# BRAIN_Breakout_routed.net
KiCad netlist of a schematic drawn in EAGLE
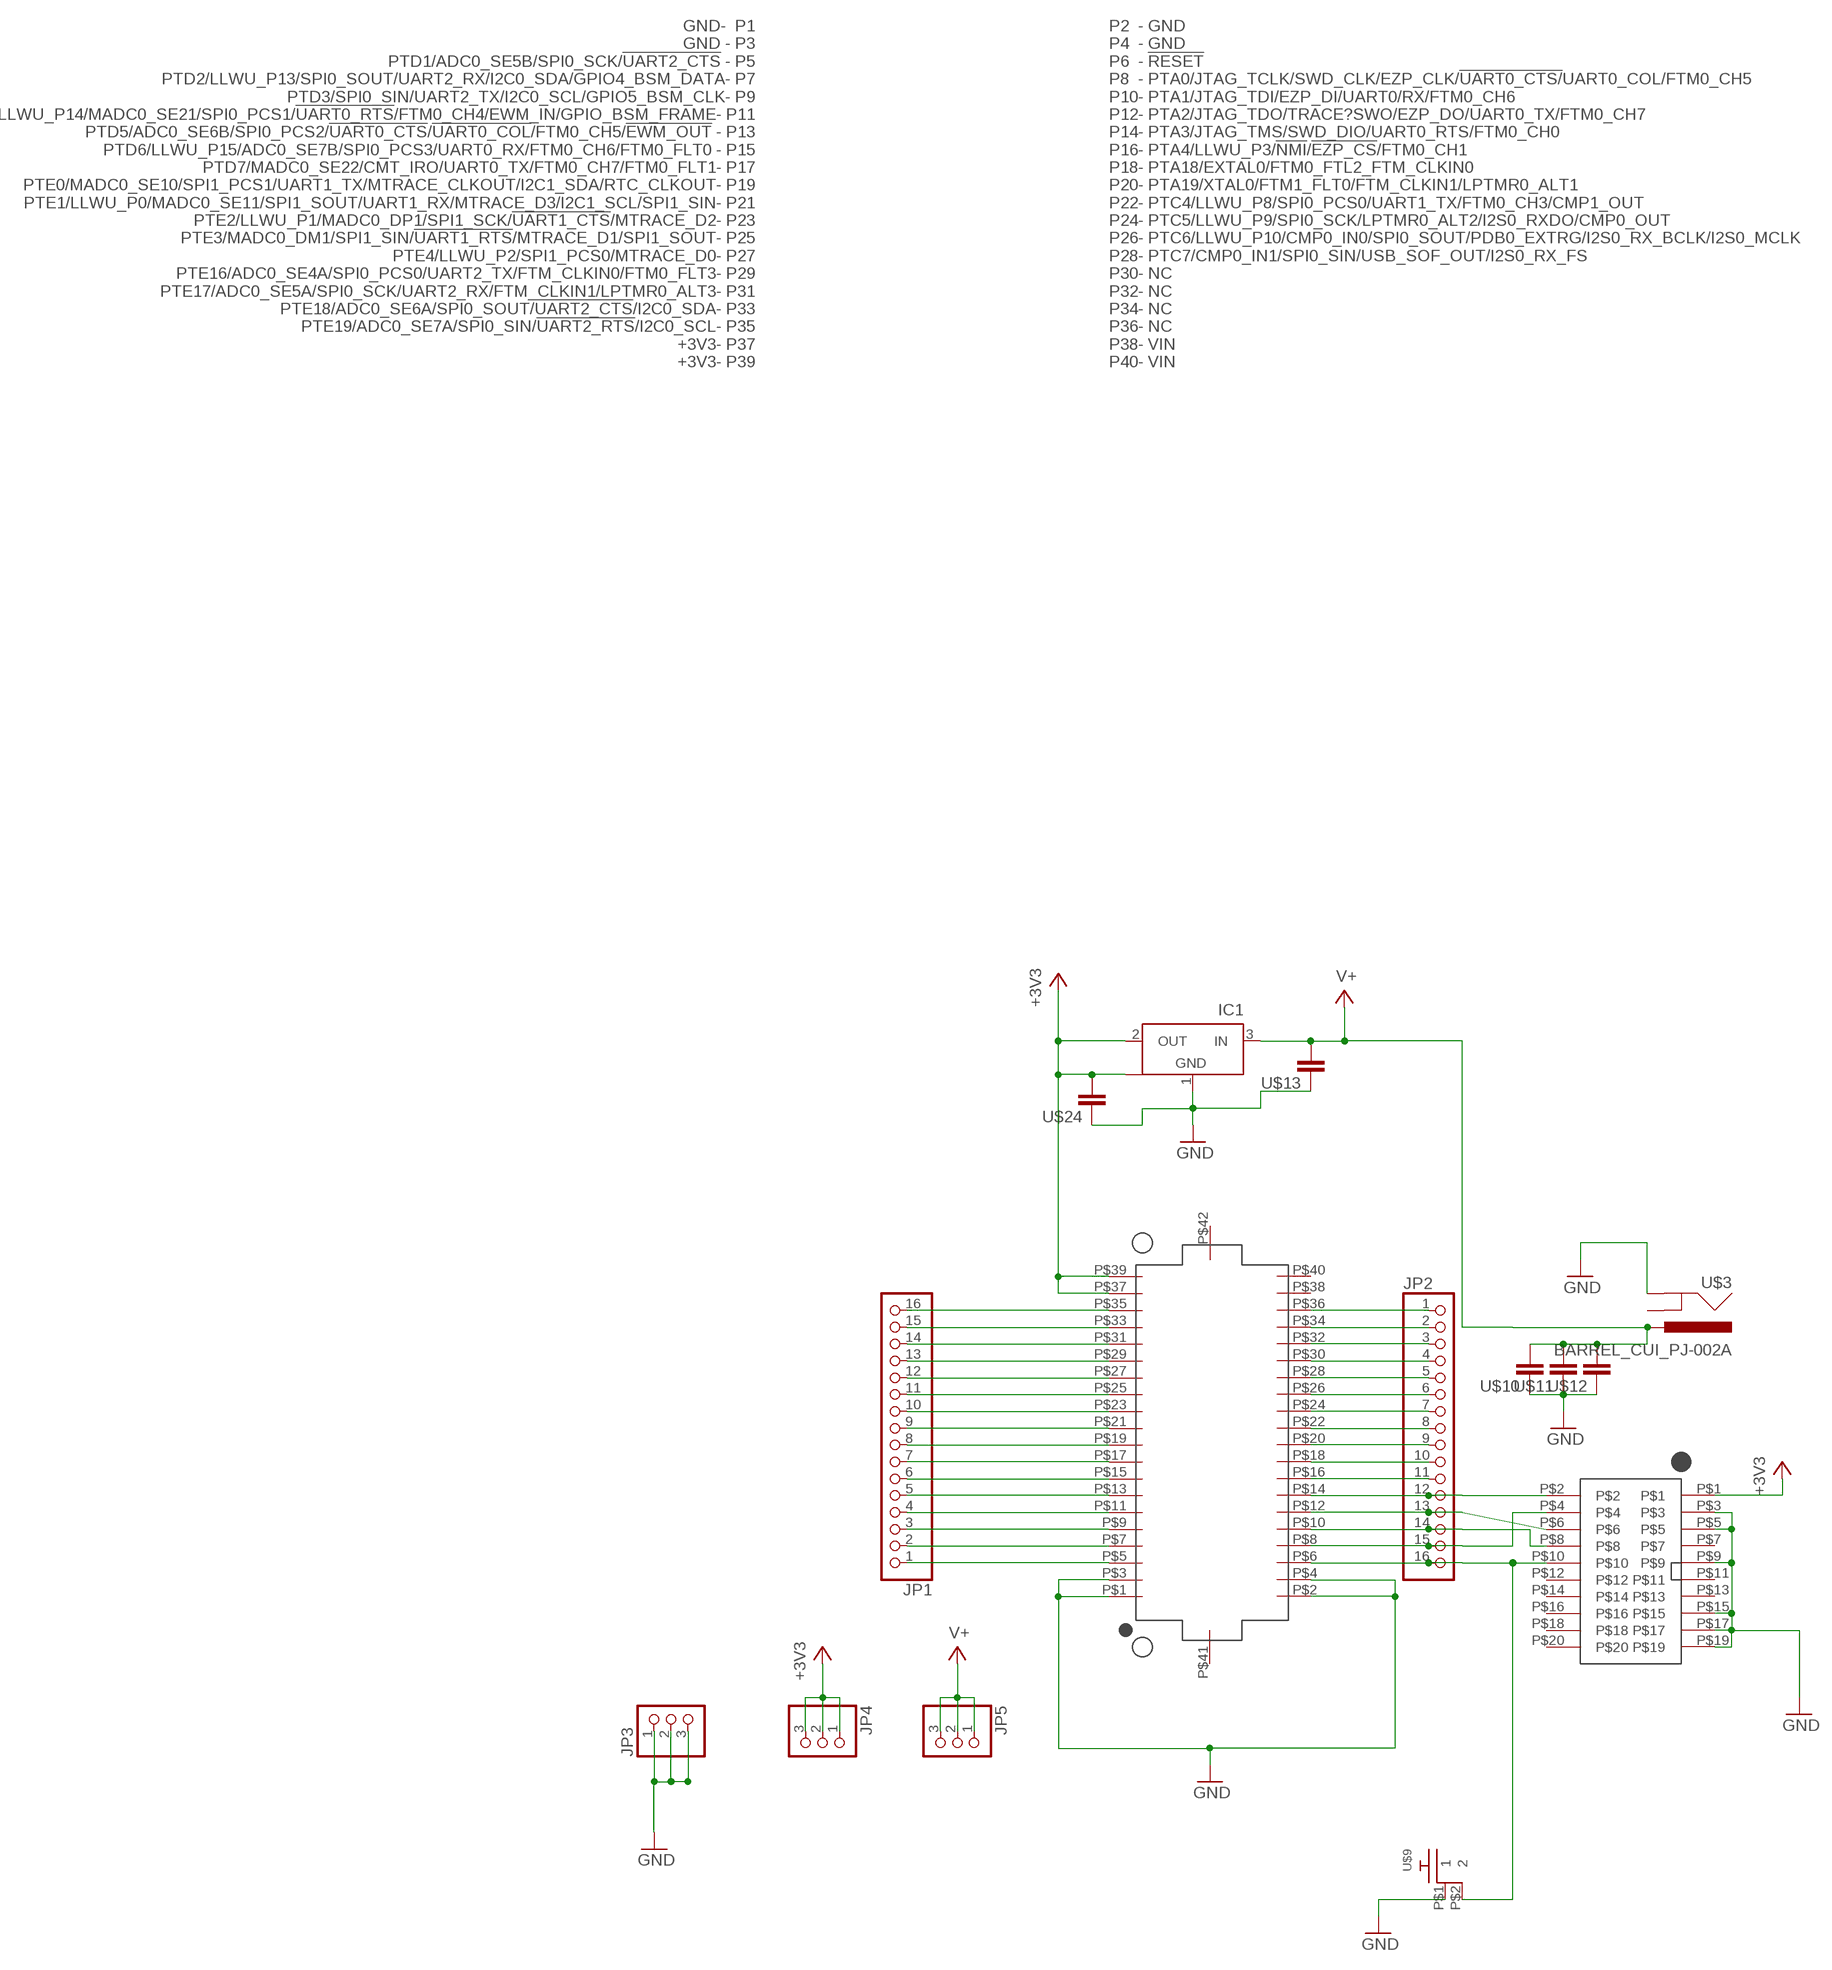
[diagram p0: schematic, sheet 1]

(export (version "E")
  (design (tool "Eeschema 10.0.6"))
  (components
    (comp (ref "IC1")
      (value "NCP1117ST33T3G_1")
      (footprint "eagle-import:SOT223")
      (fields (field (name "MFGN") "OnSemi") (field (name "MFGP") "NCP1117ST33T3G"))
      (libsource (lib "eagle-import") (part "NCP1117ST33T3G_1"))
    )
    (comp (ref "JP1")
      (value "PINHD-1X16")
      (footprint "eagle-import:1X16")
      (libsource (lib "eagle-import") (part "PINHD-1X16"))
    )
    (comp (ref "JP2")
      (value "PINHD-1X16")
      (footprint "eagle-import:1X16")
      (libsource (lib "eagle-import") (part "PINHD-1X16"))
    )
    (comp (ref "JP3")
      (value "PINHD-1X3")
      (footprint "eagle-import:1X03")
      (libsource (lib "eagle-import") (part "PINHD-1X3"))
    )
    (comp (ref "JP4")
      (value "PINHD-1X3")
      (footprint "eagle-import:1X03")
      (libsource (lib "eagle-import") (part "PINHD-1X3"))
    )
    (comp (ref "JP5")
      (value "PINHD-1X3")
      (footprint "eagle-import:1X03")
      (libsource (lib "eagle-import") (part "PINHD-1X3"))
    )
    (comp (ref "U$1")
      (value "DF12_F")
      (footprint "eagle-import:DF12_F")
      (libsource (lib "eagle-import") (part "DF12_F"))
    )
    (comp (ref "U$3")
      (value "BARREL_CUI_PJ-002A")
      (footprint "eagle-import:BARREL_CUI_PJ-002A")
      (libsource (lib "eagle-import") (part "BARREL_CUI_PJ-002A"))
    )
    (comp (ref "U$9")
      (value "RA_BUTTON")
      (footprint "eagle-import:RA_BUTTON")
      (libsource (lib "eagle-import") (part "RA_BUTTON"))
    )
    (comp (ref "U$10")
      (value "RF-C0805")
      (footprint "eagle-import:C0805")
      (libsource (lib "eagle-import") (part "RF-C0805"))
    )
    (comp (ref "U$11")
      (value "RF-C0805")
      (footprint "eagle-import:C0805")
      (libsource (lib "eagle-import") (part "RF-C0805"))
    )
    (comp (ref "U$12")
      (value "RF-C0805")
      (footprint "eagle-import:C0805")
      (libsource (lib "eagle-import") (part "RF-C0805"))
    )
    (comp (ref "U$13")
      (value "RF-C0805")
      (footprint "eagle-import:C0805")
      (libsource (lib "eagle-import") (part "RF-C0805"))
    )
    (comp (ref "U$19")
      (value "2X10JTAG")
      (footprint "eagle-import:2X10JTAG")
      (libsource (lib "eagle-import") (part "2X10JTAG"))
    )
    (comp (ref "U$24")
      (value "RF-C0805")
      (footprint "eagle-import:C0805")
      (libsource (lib "eagle-import") (part "RF-C0805"))
    )
  )
  (nets
    (net (code "1") (name "+3V3") (class "Default")
      (node (ref "IC1") (pin "2") (pinfunction "OUT_2") (pintype "power_in"))
      (node (ref "IC1") (pin "4") (pinfunction "OUT1_4") (pintype "power_in"))
      (node (ref "JP4") (pin "1") (pinfunction "1_1") (pintype "passive"))
      (node (ref "JP4") (pin "2") (pinfunction "2_2") (pintype "passive"))
      (node (ref "JP4") (pin "3") (pinfunction "3_3") (pintype "passive"))
      (node (ref "U$1") (pin "P$37") (pinfunction "+3V3_P$37") (pintype "bidirectional"))
      (node (ref "U$1") (pin "P$39") (pinfunction "+3V3_P$39") (pintype "bidirectional"))
      (node (ref "U$19") (pin "P$1") (pinfunction "P$1_P$1") (pintype "bidirectional"))
      (node (ref "U$24") (pin "2") (pinfunction "2_2") (pintype "passive"))
    )
    (net (code "2") (name "GND") (class "Default")
      (node (ref "IC1") (pin "1") (pinfunction "GND_1") (pintype "power_in"))
      (node (ref "JP3") (pin "1") (pinfunction "1_1") (pintype "passive"))
      (node (ref "JP3") (pin "2") (pinfunction "2_2") (pintype "passive"))
      (node (ref "JP3") (pin "3") (pinfunction "3_3") (pintype "passive"))
      (node (ref "U$1") (pin "P$1") (pinfunction "GND_P$1") (pintype "bidirectional"))
      (node (ref "U$1") (pin "P$2") (pinfunction "GND_P$2") (pintype "bidirectional"))
      (node (ref "U$1") (pin "P$3") (pinfunction "GND_P$3") (pintype "bidirectional"))
      (node (ref "U$1") (pin "P$4") (pinfunction "GND_P$4") (pintype "bidirectional"))
      (node (ref "U$10") (pin "1") (pinfunction "1_1") (pintype "passive"))
      (node (ref "U$11") (pin "1") (pinfunction "1_1") (pintype "passive"))
      (node (ref "U$12") (pin "1") (pinfunction "1_1") (pintype "passive"))
      (node (ref "U$13") (pin "1") (pinfunction "1_1") (pintype "passive"))
      (node (ref "U$19") (pin "P$15") (pinfunction "P$15_P$15") (pintype "bidirectional"))
      (node (ref "U$19") (pin "P$17") (pinfunction "P$17_P$17") (pintype "bidirectional"))
      (node (ref "U$19") (pin "P$19") (pinfunction "P$19_P$19") (pintype "bidirectional"))
      (node (ref "U$19") (pin "P$3") (pinfunction "P$3_P$3") (pintype "bidirectional"))
      (node (ref "U$19") (pin "P$5") (pinfunction "P$5_P$5") (pintype "bidirectional"))
      (node (ref "U$19") (pin "P$9") (pinfunction "P$9_P$9") (pintype "bidirectional"))
      (node (ref "U$24") (pin "1") (pinfunction "1_1") (pintype "passive"))
      (node (ref "U$3") (pin "P$2") (pinfunction "GND_P$2") (pintype "bidirectional"))
      (node (ref "U$9") (pin "P$1") (pinfunction "1_P$1") (pintype "input"))
    )
    (net (code "3") (name "Net-(JP2-Pad1)") (class "Default")
      (node (ref "JP2") (pin "1") (pinfunction "1_1") (pintype "passive"))
      (node (ref "U$1") (pin "P$36") (pinfunction "NC_P$36") (pintype "bidirectional"))
    )
    (net (code "4") (name "Net-(JP2-Pad2)") (class "Default")
      (node (ref "JP2") (pin "2") (pinfunction "2_2") (pintype "passive"))
      (node (ref "U$1") (pin "P$34") (pinfunction "NC_P$34") (pintype "bidirectional"))
    )
    (net (code "5") (name "Net-(JP2-Pad3)") (class "Default")
      (node (ref "JP2") (pin "3") (pinfunction "3_3") (pintype "passive"))
      (node (ref "U$1") (pin "P$32") (pinfunction "NC_P$32") (pintype "bidirectional"))
    )
    (net (code "6") (name "Net-(JP2-Pad4)") (class "Default")
      (node (ref "JP2") (pin "4") (pinfunction "4_4") (pintype "passive"))
      (node (ref "U$1") (pin "P$30") (pinfunction "NC_P$30") (pintype "bidirectional"))
    )
    (net (code "7") (name "Net-(U$1-PTA0{slash}JTAG_TCLK{slash}SWD_CLK{slash}EZP_CLK{slash}~{UART0_CTS{slash}}UART0_COL{slash}FTM0_CH5)") (class "Default")
      (node (ref "JP2") (pin "15") (pinfunction "15_15") (pintype "passive"))
      (node (ref "U$1") (pin "P$8") (pinfunction "PTA0/JTAG_TCLK/SWD_CLK/EZP_CLK/~{UART0_CTS/}UART0_COL/FTM0_CH5_P$8") (pintype "bidirectional"))
      (node (ref "U$19") (pin "P$4") (pinfunction "P$4_P$4") (pintype "bidirectional"))
    )
    (net (code "8") (name "Net-(U$1-PTA1{slash}JTAG_TDI{slash}EZP_DI{slash}UART0{slash}RX{slash}FTM0_CH6)") (class "Default")
      (node (ref "JP2") (pin "14") (pinfunction "14_14") (pintype "passive"))
      (node (ref "U$1") (pin "P$10") (pinfunction "PTA1/JTAG_TDI/EZP_DI/UART0/RX/FTM0_CH6_P$10") (pintype "bidirectional"))
      (node (ref "U$19") (pin "P$8") (pinfunction "P$8_P$8") (pintype "bidirectional"))
    )
    (net (code "9") (name "Net-(U$1-PTA2{slash}JTAG_TDO{slash}TRACE?SWO{slash}EZP_DO{slash}UART0_TX{slash}FTM0_CH7)") (class "Default")
      (node (ref "JP2") (pin "13") (pinfunction "13_13") (pintype "passive"))
      (node (ref "U$1") (pin "P$12") (pinfunction "PTA2/JTAG_TDO/TRACE?SWO/EZP_DO/UART0_TX/FTM0_CH7_P$12") (pintype "bidirectional"))
      (node (ref "U$19") (pin "P$6") (pinfunction "P$6_P$6") (pintype "bidirectional"))
    )
    (net (code "10") (name "Net-(U$1-PTA3{slash}JTAG_TMS{slash}SWD_DIO{slash}UART0_RTS{slash}FTM0_CH0)") (class "Default")
      (node (ref "JP2") (pin "12") (pinfunction "12_12") (pintype "passive"))
      (node (ref "U$1") (pin "P$14") (pinfunction "PTA3/JTAG_TMS/SWD_DIO/UART0_RTS/FTM0_CH0_P$14") (pintype "bidirectional"))
      (node (ref "U$19") (pin "P$2") (pinfunction "P$2_P$2") (pintype "bidirectional"))
    )
    (net (code "11") (name "Net-(U$1-PTA4{slash}LLWU_P3{slash}~{NMI}{slash}~{EZP_CS}{slash}FTM0_CH1)") (class "Default")
      (node (ref "JP2") (pin "11") (pinfunction "11_11") (pintype "passive"))
      (node (ref "U$1") (pin "P$16") (pinfunction "PTA4/LLWU_P3/~{NMI}/~{EZP_CS}/FTM0_CH1_P$16") (pintype "bidirectional"))
    )
    (net (code "12") (name "Net-(U$1-PTA18{slash}EXTAL0{slash}FTM0_FTL2_FTM_CLKIN0)") (class "Default")
      (node (ref "JP2") (pin "10") (pinfunction "10_10") (pintype "passive"))
      (node (ref "U$1") (pin "P$18") (pinfunction "PTA18/EXTAL0/FTM0_FTL2_FTM_CLKIN0_P$18") (pintype "bidirectional"))
    )
    (net (code "13") (name "Net-(U$1-PTA19{slash}XTAL0{slash}FTM1_FLT0{slash}FTM_CLKIN1{slash}LPTMR0_ALT1)") (class "Default")
      (node (ref "JP2") (pin "9") (pinfunction "9_9") (pintype "passive"))
      (node (ref "U$1") (pin "P$20") (pinfunction "PTA19/XTAL0/FTM1_FLT0/FTM_CLKIN1/LPTMR0_ALT1_P$20") (pintype "bidirectional"))
    )
    (net (code "14") (name "Net-(U$1-PTC4{slash}LLWU_P8{slash}SPI0_PCS0{slash}UART1_TX{slash}FTM0_CH3{slash}CMP1_OUT)") (class "Default")
      (node (ref "JP2") (pin "8") (pinfunction "8_8") (pintype "passive"))
      (node (ref "U$1") (pin "P$22") (pinfunction "PTC4/LLWU_P8/SPI0_PCS0/UART1_TX/FTM0_CH3/CMP1_OUT_P$22") (pintype "bidirectional"))
    )
    (net (code "15") (name "Net-(U$1-PTC5{slash}LLWU_P8{slash}SPI0_PCS0{slash}UART1_TX{slash}FTM0_CH3{slash}CMP1_OUT)") (class "Default")
      (node (ref "JP2") (pin "7") (pinfunction "7_7") (pintype "passive"))
      (node (ref "U$1") (pin "P$24") (pinfunction "PTC5/LLWU_P8/SPI0_PCS0/UART1_TX/FTM0_CH3/CMP1_OUT_P$24") (pintype "bidirectional"))
    )
    (net (code "16") (name "Net-(U$1-PTC6{slash}LLWU_P10{slash}CMP0_IN0{slash}SPI0_SOUT{slash}PDB0_EXTRG{slash}I2S0_RX_BCLK{slash}I2S0_MCLK)") (class "Default")
      (node (ref "JP2") (pin "6") (pinfunction "6_6") (pintype "passive"))
      (node (ref "U$1") (pin "P$26") (pinfunction "PTC6/LLWU_P10/CMP0_IN0/SPI0_SOUT/PDB0_EXTRG/I2S0_RX_BCLK/I2S0_MCLK_P$26") (pintype "bidirectional"))
    )
    (net (code "17") (name "Net-(U$1-PTC7{slash}CMP0_IN1{slash}SPI0_SIN{slash}USB_SOF_OUT{slash}I2S0_RX_FS)") (class "Default")
      (node (ref "JP2") (pin "5") (pinfunction "5_5") (pintype "passive"))
      (node (ref "U$1") (pin "P$28") (pinfunction "PTC7/CMP0_IN1/SPI0_SIN/USB_SOF_OUT/I2S0_RX_FS_P$28") (pintype "bidirectional"))
    )
    (net (code "18") (name "Net-(U$1-PTD1{slash}ADC0_SE5B{slash}SPI0_SCK{slash}~{UART2_CTS})") (class "Default")
      (node (ref "JP1") (pin "1") (pinfunction "1_1") (pintype "passive"))
      (node (ref "U$1") (pin "P$5") (pinfunction "PTD1/ADC0_SE5B/SPI0_SCK/~{UART2_CTS}_P$5") (pintype "bidirectional"))
    )
    (net (code "19") (name "Net-(U$1-PTD2{slash}LLWU_P13{slash}SPI0_SOUT{slash}UART2_RX{slash}I2C0_SDA{slash}GPIO4_BSM_DATA)") (class "Default")
      (node (ref "JP1") (pin "2") (pinfunction "2_2") (pintype "passive"))
      (node (ref "U$1") (pin "P$7") (pinfunction "PTD2/LLWU_P13/SPI0_SOUT/UART2_RX/I2C0_SDA/GPIO4_BSM_DATA_P$7") (pintype "bidirectional"))
    )
    (net (code "20") (name "Net-(U$1-PTD3{slash}SPI0_SIN{slash}UART2_TX{slash}I2C0_SCL{slash}GPIO5_BSM_CLK)") (class "Default")
      (node (ref "JP1") (pin "3") (pinfunction "3_3") (pintype "passive"))
      (node (ref "U$1") (pin "P$9") (pinfunction "PTD3/SPI0_SIN/UART2_TX/I2C0_SCL/GPIO5_BSM_CLK_P$9") (pintype "bidirectional"))
    )
    (net (code "21") (name "Net-(U$1-PTD4{slash}LLWU_P14{slash}MADC0_SE21{slash}SPI0_PCS1{slash}~{UART0_RTS}{slash}FTM0_CH4{slash}EWM_IN{slash}GPIO_BSM_FRAME)") (class "Default")
      (node (ref "JP1") (pin "4") (pinfunction "4_4") (pintype "passive"))
      (node (ref "U$1") (pin "P$11") (pinfunction "PTD4/LLWU_P14/MADC0_SE21/SPI0_PCS1/~{UART0_RTS}/FTM0_CH4/EWM_IN/GPIO_BSM_FRAME_P$11") (pintype "bidirectional"))
    )
    (net (code "22") (name "Net-(U$1-PTD5{slash}ADC0_SE6B{slash}SPI0_PCS2{slash}~{UART0_CTS}{slash}~{UART0_COL}{slash}FTM0_CH5{slash}~{EWM_OUT})") (class "Default")
      (node (ref "JP1") (pin "5") (pinfunction "5_5") (pintype "passive"))
      (node (ref "U$1") (pin "P$13") (pinfunction "PTD5/ADC0_SE6B/SPI0_PCS2/~{UART0_CTS}/~{UART0_COL}/FTM0_CH5/~{EWM_OUT}_P$13") (pintype "bidirectional"))
    )
    (net (code "23") (name "Net-(U$1-PTD6{slash}LLWU_P15{slash}ADC0_SE7B{slash}SPI0_PCS3{slash}UART0_RX{slash}FTM0_CH6{slash}FTM0_FLT0)") (class "Default")
      (node (ref "JP1") (pin "6") (pinfunction "6_6") (pintype "passive"))
      (node (ref "U$1") (pin "P$15") (pinfunction "PTD6/LLWU_P15/ADC0_SE7B/SPI0_PCS3/UART0_RX/FTM0_CH6/FTM0_FLT0_P$15") (pintype "bidirectional"))
    )
    (net (code "24") (name "Net-(U$1-PTD7{slash}MADC0_SE22{slash}CMT_IRO{slash}UART0_TX{slash}FTM0_CH7{slash}FTM0_FLT1)") (class "Default")
      (node (ref "JP1") (pin "7") (pinfunction "7_7") (pintype "passive"))
      (node (ref "U$1") (pin "P$17") (pinfunction "PTD7/MADC0_SE22/CMT_IRO/UART0_TX/FTM0_CH7/FTM0_FLT1_P$17") (pintype "bidirectional"))
    )
    (net (code "25") (name "Net-(U$1-PTE0{slash}MADC0_SE10{slash}SPI1_PCS1{slash}UART1_TX{slash}MTRACE_CLKOUT{slash}I2C1_SDA{slash}RTC_CLKOUT)") (class "Default")
      (node (ref "JP1") (pin "8") (pinfunction "8_8") (pintype "passive"))
      (node (ref "U$1") (pin "P$19") (pinfunction "PTE0/MADC0_SE10/SPI1_PCS1/UART1_TX/MTRACE_CLKOUT/I2C1_SDA/RTC_CLKOUT_P$19") (pintype "bidirectional"))
    )
    (net (code "26") (name "Net-(U$1-PTE1{slash}LLWU_P0{slash}MADC0_SE11{slash}SPI1_SOUT{slash}UART1_RX{slash}MTRACE_D3{slash}I2C1_SCL{slash}SPI1_SIN)") (class "Default")
      (node (ref "JP1") (pin "9") (pinfunction "9_9") (pintype "passive"))
      (node (ref "U$1") (pin "P$21") (pinfunction "PTE1/LLWU_P0/MADC0_SE11/SPI1_SOUT/UART1_RX/MTRACE_D3/I2C1_SCL/SPI1_SIN_P$21") (pintype "bidirectional"))
    )
    (net (code "27") (name "Net-(U$1-PTE2{slash}LLWU_P1{slash}MADC0_DP1{slash}SPI1_SCK{slash}~{UART1_CTS}{slash}MTRACE_D2)") (class "Default")
      (node (ref "JP1") (pin "10") (pinfunction "10_10") (pintype "passive"))
      (node (ref "U$1") (pin "P$23") (pinfunction "PTE2/LLWU_P1/MADC0_DP1/SPI1_SCK/~{UART1_CTS}/MTRACE_D2_P$23") (pintype "bidirectional"))
    )
    (net (code "28") (name "Net-(U$1-PTE3{slash}MADC0_DM1{slash}SPI1_SIN{slash}~{UART1_RTS}{slash}MTRACE_D1{slash}SPI1_SOUT)") (class "Default")
      (node (ref "JP1") (pin "11") (pinfunction "11_11") (pintype "passive"))
      (node (ref "U$1") (pin "P$25") (pinfunction "PTE3/MADC0_DM1/SPI1_SIN/~{UART1_RTS}/MTRACE_D1/SPI1_SOUT_P$25") (pintype "bidirectional"))
    )
    (net (code "29") (name "Net-(U$1-PTE4{slash}LLWU_P2{slash}SPI1_PCS0{slash}MTRACE_D0)") (class "Default")
      (node (ref "JP1") (pin "12") (pinfunction "12_12") (pintype "passive"))
      (node (ref "U$1") (pin "P$27") (pinfunction "PTE4/LLWU_P2/SPI1_PCS0/MTRACE_D0_P$27") (pintype "bidirectional"))
    )
    (net (code "30") (name "Net-(U$1-PTE16{slash}ADC0_SE4A{slash}SPI0_PCS0{slash}UART2_TX{slash}FTM_CLKIN0{slash}FTM0_FLT3)") (class "Default")
      (node (ref "JP1") (pin "13") (pinfunction "13_13") (pintype "passive"))
      (node (ref "U$1") (pin "P$29") (pinfunction "PTE16/ADC0_SE4A/SPI0_PCS0/UART2_TX/FTM_CLKIN0/FTM0_FLT3_P$29") (pintype "bidirectional"))
    )
    (net (code "31") (name "Net-(U$1-PTE17{slash}ADC0_SE5A{slash}SPI0_SCK{slash}UART2_RX{slash}FTM_CLKIN1{slash}LPTMR0_ALT3)") (class "Default")
      (node (ref "JP1") (pin "14") (pinfunction "14_14") (pintype "passive"))
      (node (ref "U$1") (pin "P$31") (pinfunction "PTE17/ADC0_SE5A/SPI0_SCK/UART2_RX/FTM_CLKIN1/LPTMR0_ALT3_P$31") (pintype "bidirectional"))
    )
    (net (code "32") (name "Net-(U$1-PTE18{slash}ADC0_SE6A{slash}SPI0_SOUT{slash}~{UART2_CTS}{slash}I2C0_SDA)") (class "Default")
      (node (ref "JP1") (pin "15") (pinfunction "15_15") (pintype "passive"))
      (node (ref "U$1") (pin "P$33") (pinfunction "PTE18/ADC0_SE6A/SPI0_SOUT/~{UART2_CTS}/I2C0_SDA_P$33") (pintype "bidirectional"))
    )
    (net (code "33") (name "Net-(U$1-PTE19{slash}ADC0_SE7A{slash}SPI0_SIN{slash}~{UART2_RTS}{slash}I2C0_SCL)") (class "Default")
      (node (ref "JP1") (pin "16") (pinfunction "16_16") (pintype "passive"))
      (node (ref "U$1") (pin "P$35") (pinfunction "PTE19/ADC0_SE7A/SPI0_SIN/~{UART2_RTS}/I2C0_SCL_P$35") (pintype "bidirectional"))
    )
    (net (code "34") (name "Net-(U$1-~{RESET})") (class "Default")
      (node (ref "JP2") (pin "16") (pinfunction "16_16") (pintype "passive"))
      (node (ref "U$1") (pin "P$6") (pinfunction "~{RESET}_P$6") (pintype "bidirectional"))
      (node (ref "U$19") (pin "P$10") (pinfunction "P$10_P$10") (pintype "bidirectional"))
      (node (ref "U$9") (pin "P$2") (pinfunction "2_P$2") (pintype "input"))
    )
    (net (code "35") (name "V+") (class "Default")
      (node (ref "IC1") (pin "3") (pinfunction "IN_3") (pintype "input"))
      (node (ref "JP5") (pin "1") (pinfunction "1_1") (pintype "passive"))
      (node (ref "JP5") (pin "2") (pinfunction "2_2") (pintype "passive"))
      (node (ref "JP5") (pin "3") (pinfunction "3_3") (pintype "passive"))
      (node (ref "U$10") (pin "2") (pinfunction "2_2") (pintype "passive"))
      (node (ref "U$11") (pin "2") (pinfunction "2_2") (pintype "passive"))
      (node (ref "U$12") (pin "2") (pinfunction "2_2") (pintype "passive"))
      (node (ref "U$13") (pin "2") (pinfunction "2_2") (pintype "passive"))
      (node (ref "U$3") (pin "P$1") (pinfunction "PWR_P$1") (pintype "bidirectional"))
    )
    (net (code "36") (name "unconnected-(U$1-PadP$41)") (class "Default")
      (node (ref "U$1") (pin "P$41") (pinfunction "P$41_P$41") (pintype "bidirectional"))
    )
    (net (code "37") (name "unconnected-(U$1-PadP$42)") (class "Default")
      (node (ref "U$1") (pin "P$42") (pinfunction "P$42_P$42") (pintype "bidirectional"))
    )
    (net (code "38") (name "unconnected-(U$1-VIN-PadP$38)") (class "Default")
      (node (ref "U$1") (pin "P$38") (pinfunction "VIN_P$38") (pintype "bidirectional"))
    )
    (net (code "39") (name "unconnected-(U$1-VIN-PadP$40)") (class "Default")
      (node (ref "U$1") (pin "P$40") (pinfunction "VIN_P$40") (pintype "bidirectional"))
    )
    (net (code "40") (name "unconnected-(U$3-GNDBREAK-PadP$3)") (class "Default")
      (node (ref "U$3") (pin "P$3") (pinfunction "GNDBREAK_P$3") (pintype "bidirectional"))
    )
    (net (code "41") (name "unconnected-(U$19-PadP$7)") (class "Default")
      (node (ref "U$19") (pin "P$7") (pinfunction "P$7_P$7") (pintype "bidirectional"))
    )
    (net (code "42") (name "unconnected-(U$19-PadP$11)") (class "Default")
      (node (ref "U$19") (pin "P$11") (pinfunction "P$11_P$11") (pintype "bidirectional"))
    )
    (net (code "43") (name "unconnected-(U$19-PadP$12)") (class "Default")
      (node (ref "U$19") (pin "P$12") (pinfunction "P$12_P$12") (pintype "bidirectional"))
    )
    (net (code "44") (name "unconnected-(U$19-PadP$13)") (class "Default")
      (node (ref "U$19") (pin "P$13") (pinfunction "P$13_P$13") (pintype "bidirectional"))
    )
    (net (code "45") (name "unconnected-(U$19-PadP$14)") (class "Default")
      (node (ref "U$19") (pin "P$14") (pinfunction "P$14_P$14") (pintype "bidirectional"))
    )
    (net (code "46") (name "unconnected-(U$19-PadP$16)") (class "Default")
      (node (ref "U$19") (pin "P$16") (pinfunction "P$16_P$16") (pintype "bidirectional"))
    )
    (net (code "47") (name "unconnected-(U$19-PadP$18)") (class "Default")
      (node (ref "U$19") (pin "P$18") (pinfunction "P$18_P$18") (pintype "bidirectional"))
    )
    (net (code "48") (name "unconnected-(U$19-PadP$20)") (class "Default")
      (node (ref "U$19") (pin "P$20") (pinfunction "P$20_P$20") (pintype "bidirectional"))
    )
  )
)
